# ESP8266MDL.net
KiCad netlist of a schematic drawn in EAGLE
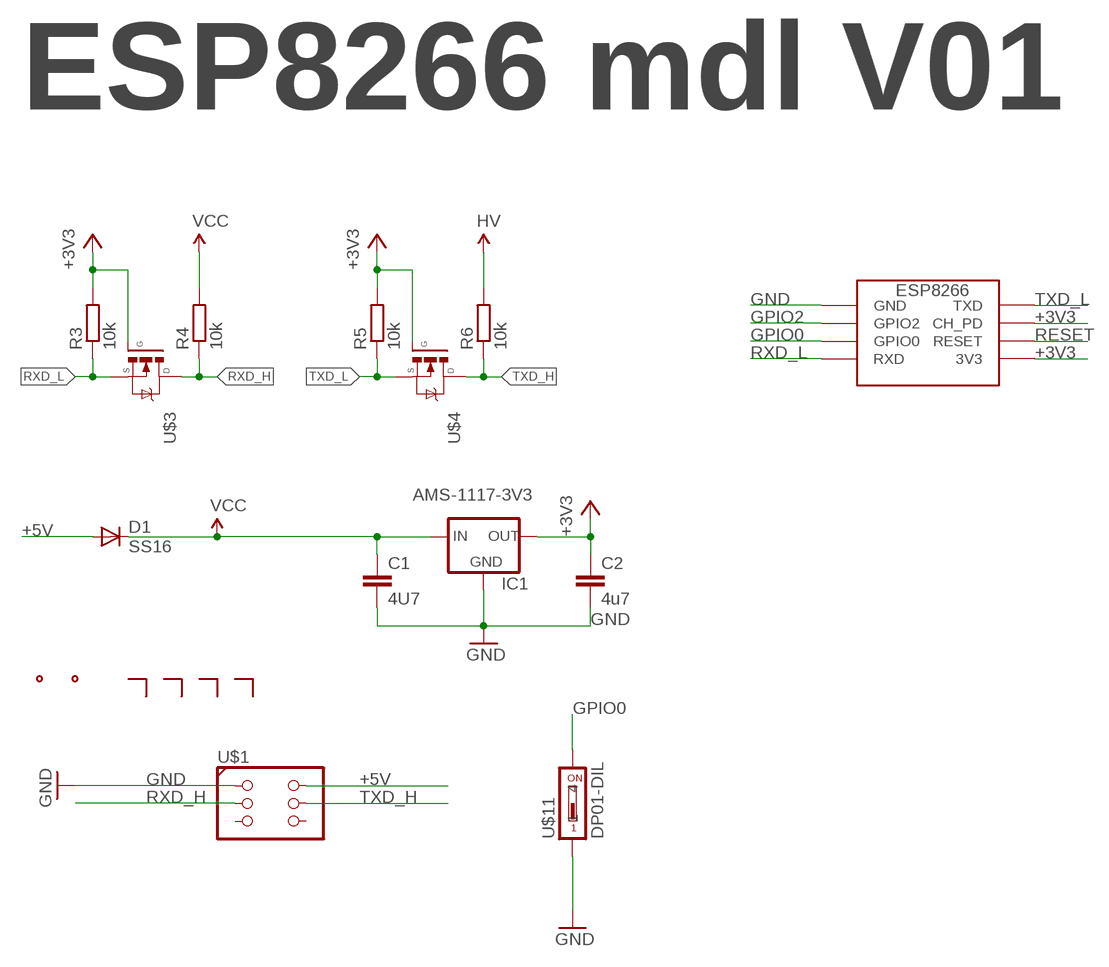
[diagram p0: schematic, sheet 1]

(export (version "E")
  (design (tool "Eeschema 10.0.6"))
  (components
    (comp (ref "C1")
      (value "4U7")
      (footprint "eagle-import:C0805")
      (libsource (lib "eagle-import") (part "C-EUC0805"))
    )
    (comp (ref "C2")
      (value "4u7")
      (footprint "eagle-import:C0805")
      (libsource (lib "eagle-import") (part "C-EUC0805"))
    )
    (comp (ref "D1")
      (value "SS16")
      (footprint "eagle-import:DO214AC")
      (libsource (lib "eagle-import") (part "DIODE-DO214AC"))
    )
    (comp (ref "IC1")
      (value "AMS-1117-3V3")
      (footprint "eagle-import:SOT223")
      (libsource (lib "eagle-import") (part "LM1117"))
    )
    (comp (ref "R3")
      (value "10k")
      (footprint "eagle-import:R0805")
      (libsource (lib "eagle-import") (part "R-EU_R0805"))
    )
    (comp (ref "R4")
      (value "10k")
      (footprint "eagle-import:R0805")
      (libsource (lib "eagle-import") (part "R-EU_R0805"))
    )
    (comp (ref "R5")
      (value "10k")
      (footprint "eagle-import:R0805")
      (libsource (lib "eagle-import") (part "R-EU_R0805"))
    )
    (comp (ref "R6")
      (value "10k")
      (footprint "eagle-import:R0805")
      (libsource (lib "eagle-import") (part "R-EU_R0805"))
    )
    (comp (ref "U$1")
      (value "PINHD-2X3S")
      (footprint "eagle-import:2X03S")
      (libsource (lib "eagle-import") (part "PINHD-2X3S"))
    )
    (comp (ref "U$2")
      (value "MARKER")
      (footprint "eagle-import:MARKER")
      (libsource (lib "eagle-import") (part "MARKER"))
    )
    (comp (ref "U$3")
      (value "2N7002-S")
      (footprint "eagle-import:SOT23-FET-SMALL")
      (libsource (lib "eagle-import") (part "2N7002-S"))
    )
    (comp (ref "U$4")
      (value "2N7002-S")
      (footprint "eagle-import:SOT23-FET-SMALL")
      (libsource (lib "eagle-import") (part "2N7002-S"))
    )
    (comp (ref "U$5")
      (value "MARKER")
      (footprint "eagle-import:MARKER")
      (libsource (lib "eagle-import") (part "MARKER"))
    )
    (comp (ref "U$6")
      (value "MARKERDUAL-50")
      (footprint "eagle-import:MARKER50")
      (libsource (lib "eagle-import") (part "MARKERDUAL-50"))
    )
    (comp (ref "U$7")
      (value "ESP8266")
      (footprint "eagle-import:ESP8266")
      (libsource (lib "eagle-import") (part "ESP8266"))
    )
    (comp (ref "U$8")
      (value "MARKER")
      (footprint "eagle-import:MARKER")
      (libsource (lib "eagle-import") (part "MARKER"))
    )
    (comp (ref "U$9")
      (value "MARKER")
      (footprint "eagle-import:MARKER")
      (libsource (lib "eagle-import") (part "MARKER"))
    )
    (comp (ref "U$11")
      (value "DP01-DIL")
      (footprint "eagle-import:DP-01")
      (libsource (lib "eagle-import") (part "DP01-DIL"))
    )
  )
  (nets
    (net (code "1") (name "+3V3") (class "Default")
      (node (ref "C2") (pin "1") (pinfunction "1_1") (pintype "passive"))
      (node (ref "IC1") (pin "2") (pinfunction "OUT_2") (pintype "passive"))
      (node (ref "IC1") (pin "4") (pinfunction "OUT_4") (pintype "passive"))
      (node (ref "R3") (pin "2") (pinfunction "2_2") (pintype "passive"))
      (node (ref "R5") (pin "2") (pinfunction "2_2") (pintype "passive"))
      (node (ref "U$3") (pin "G") (pinfunction "G_G") (pintype "passive"))
      (node (ref "U$4") (pin "G") (pinfunction "G_G") (pintype "passive"))
      (node (ref "U$7") (pin "P$4") (pinfunction "CH_PD_P$4") (pintype "bidirectional"))
      (node (ref "U$7") (pin "P$8") (pinfunction "3V3_P$8") (pintype "bidirectional"))
    )
    (net (code "2") (name "/+5V") (class "Default")
      (node (ref "D1") (pin "A") (pinfunction "A_A") (pintype "passive"))
      (node (ref "U$1") (pin "2") (pinfunction "2_2") (pintype "passive"))
    )
    (net (code "3") (name "/GPIO0") (class "Default")
      (node (ref "U$11") (pin "P$2") (pinfunction "4_P$2") (pintype "passive"))
      (node (ref "U$7") (pin "P$5") (pinfunction "GPIO0_P$5") (pintype "bidirectional"))
    )
    (net (code "4") (name "/GPIO2") (class "Default")
      (node (ref "U$7") (pin "P$3") (pinfunction "GPIO2_P$3") (pintype "bidirectional"))
    )
    (net (code "5") (name "/RESET") (class "Default")
      (node (ref "U$7") (pin "P$6") (pinfunction "RESET_P$6") (pintype "bidirectional"))
    )
    (net (code "6") (name "GND") (class "Default")
      (node (ref "C1") (pin "2") (pinfunction "2_2") (pintype "passive"))
      (node (ref "C2") (pin "2") (pinfunction "2_2") (pintype "passive"))
      (node (ref "IC1") (pin "1") (pinfunction "GND_1") (pintype "input"))
      (node (ref "U$1") (pin "1") (pinfunction "1_1") (pintype "passive"))
      (node (ref "U$11") (pin "P$1") (pinfunction "1_P$1") (pintype "passive"))
      (node (ref "U$7") (pin "P$1") (pinfunction "GND_P$1") (pintype "bidirectional"))
    )
    (net (code "7") (name "HV") (class "Default")
      (node (ref "C1") (pin "1") (pinfunction "1_1") (pintype "passive"))
      (node (ref "D1") (pin "C") (pinfunction "C_C") (pintype "passive"))
      (node (ref "IC1") (pin "3") (pinfunction "IN_3") (pintype "input"))
      (node (ref "R4") (pin "2") (pinfunction "2_2") (pintype "passive"))
      (node (ref "R6") (pin "2") (pinfunction "2_2") (pintype "passive"))
    )
    (net (code "8") (name "RXD_H") (class "Default")
      (node (ref "R4") (pin "1") (pinfunction "1_1") (pintype "passive"))
      (node (ref "U$1") (pin "3") (pinfunction "3_3") (pintype "passive"))
      (node (ref "U$3") (pin "D") (pinfunction "D_D") (pintype "passive"))
    )
    (net (code "9") (name "RXD_L") (class "Default")
      (node (ref "R3") (pin "1") (pinfunction "1_1") (pintype "passive"))
      (node (ref "U$3") (pin "S") (pinfunction "S_S") (pintype "passive"))
      (node (ref "U$7") (pin "P$7") (pinfunction "RXD_P$7") (pintype "bidirectional"))
    )
    (net (code "10") (name "TXD_H") (class "Default")
      (node (ref "R6") (pin "1") (pinfunction "1_1") (pintype "passive"))
      (node (ref "U$1") (pin "4") (pinfunction "4_4") (pintype "passive"))
      (node (ref "U$4") (pin "D") (pinfunction "D_D") (pintype "passive"))
    )
    (net (code "11") (name "TXD_L") (class "Default")
      (node (ref "R5") (pin "1") (pinfunction "1_1") (pintype "passive"))
      (node (ref "U$4") (pin "S") (pinfunction "S_S") (pintype "passive"))
      (node (ref "U$7") (pin "P$2") (pinfunction "TXD_P$2") (pintype "bidirectional"))
    )
    (net (code "12") (name "unconnected-(U$1-Pad5)") (class "Default")
      (node (ref "U$1") (pin "5") (pinfunction "5_5") (pintype "passive"))
    )
    (net (code "13") (name "unconnected-(U$1-Pad6)") (class "Default")
      (node (ref "U$1") (pin "6") (pinfunction "6_6") (pintype "passive"))
    )
  )
)
